# Domino_Pi_No_Teardrop.net
KiCad netlist of a schematic drawn in EAGLE
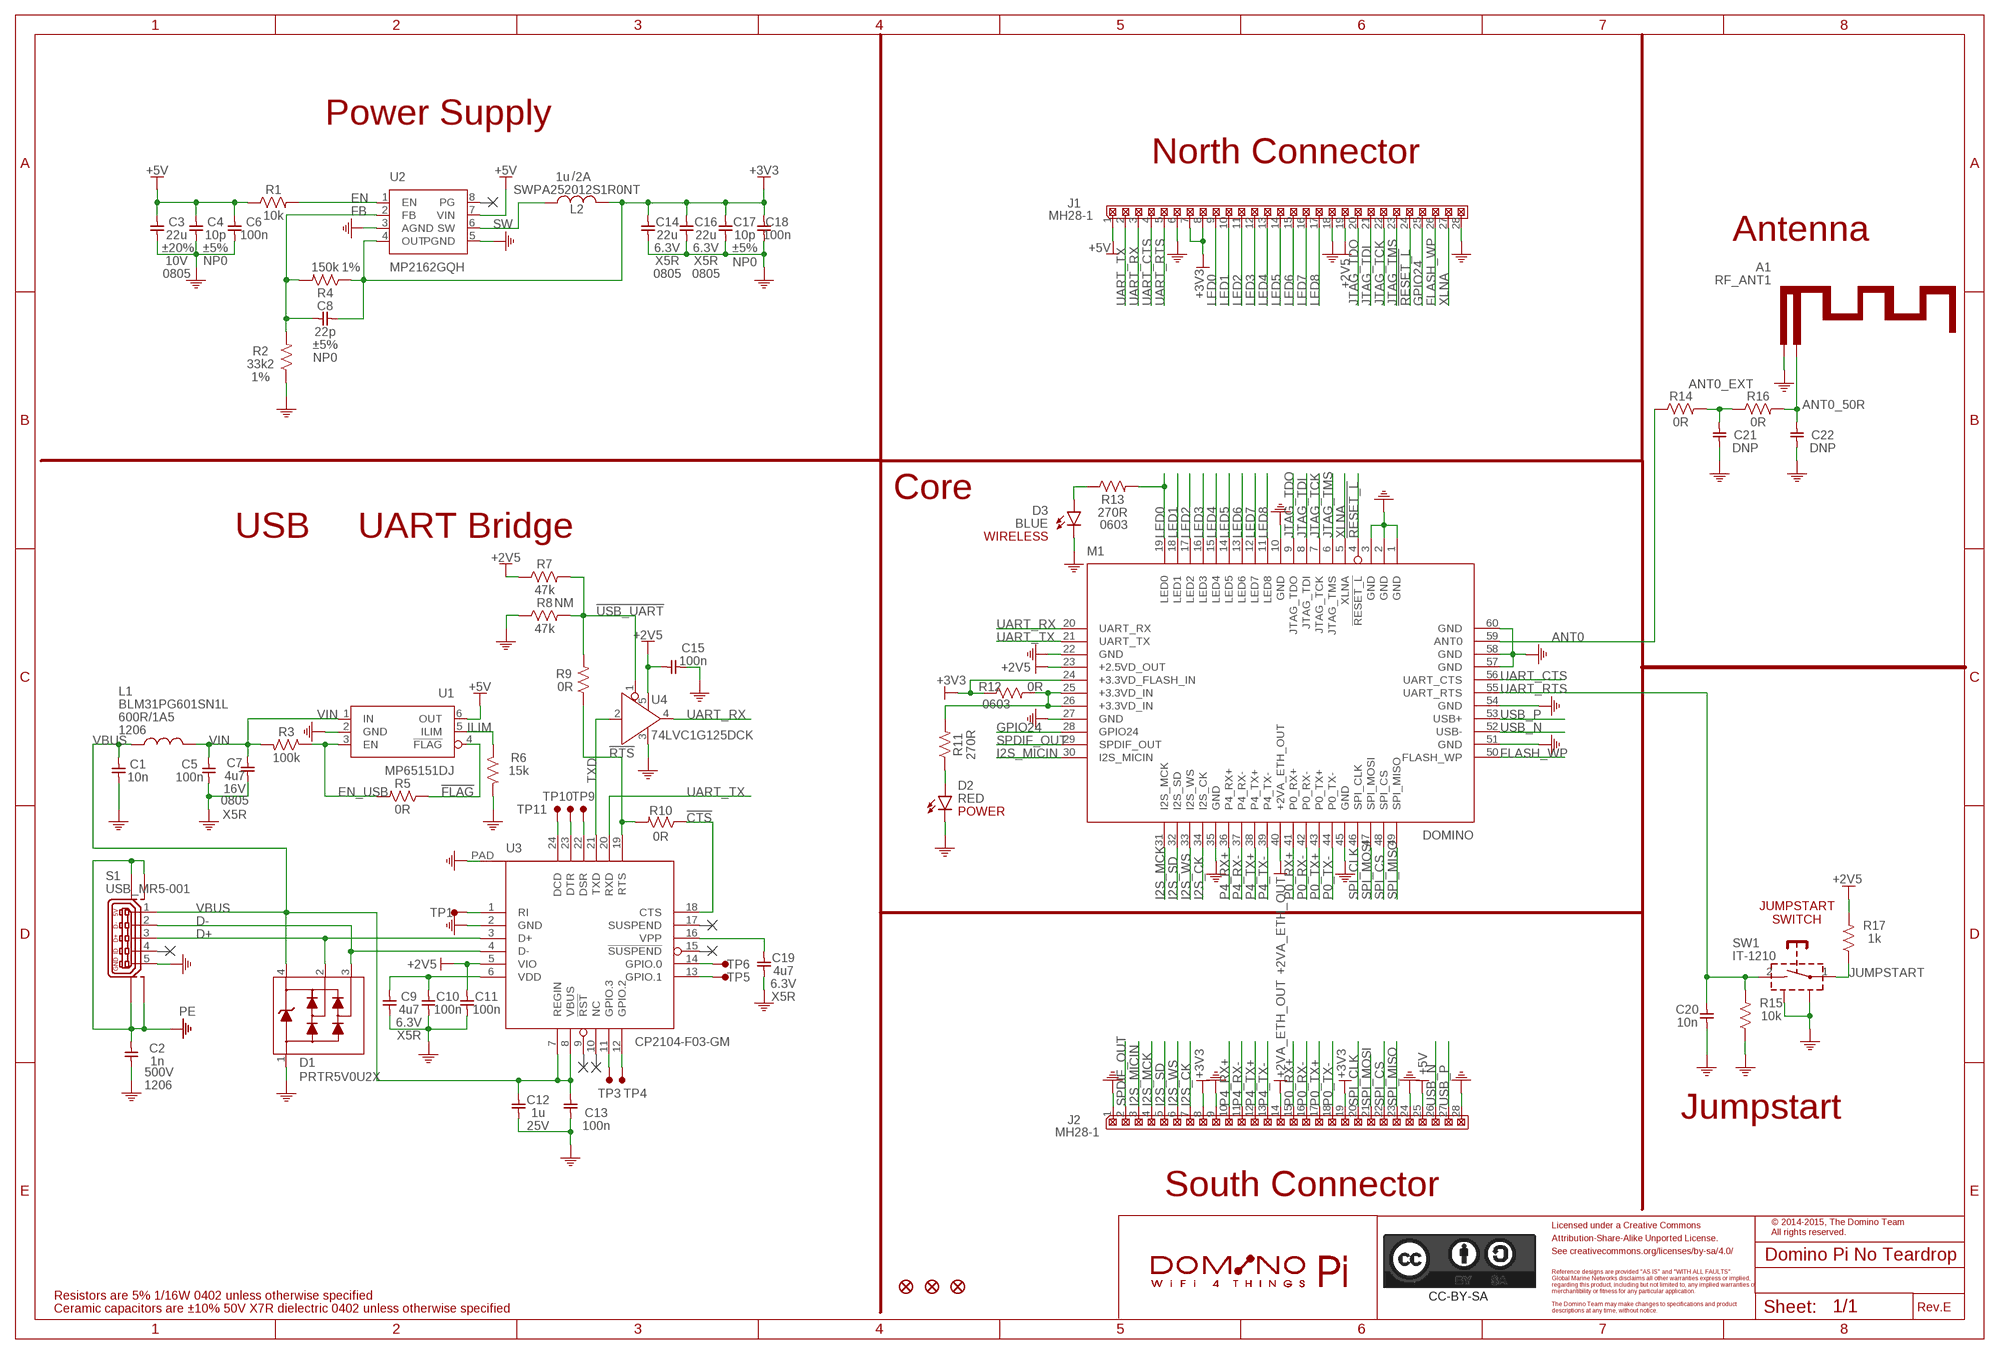
[diagram p0: schematic, sheet 1]

(export (version "E")
  (design (tool "Eeschema 10.0.6"))
  (components
    (comp (ref "A1")
      (value "RF_ANT1")
      (footprint "eagle-import:RF_ANT1")
      (fields (field (name "PARTNO") "WIFI_ANT-2.4GHz"))
      (libsource (lib "eagle-import") (part "RF_ANT1"))
    )
    (comp (ref "C1")
      (value "10n")
      (footprint "eagle-import:C0402")
      (fields (field (name "PARTNO") "C0402_10n_X7R_10%_CER_50V"))
      (libsource (lib "eagle-import") (part "CAP_0402"))
    )
    (comp (ref "C2")
      (value "1n")
      (footprint "eagle-import:C1206")
      (fields
        (field (name "SIZE") "1206")
        (field (name "PARTNO") "C1206_1n_X7R_10%_CER_500V")
        (field (name "VOLT") "500V")
      )
      (libsource (lib "eagle-import") (part "CAP_1206"))
    )
    (comp (ref "C3")
      (value "22u")
      (footprint "eagle-import:C0805")
      (fields
        (field (name "SIZE") "0805")
        (field (name "PARTNO") "C1206_22u_X7R_20%_CER_10V")
        (field (name "TOL") "±20%")
        (field (name "VOLT") "10V")
      )
      (libsource (lib "eagle-import") (part "CAP_0805"))
    )
    (comp (ref "C4")
      (value "10p")
      (footprint "eagle-import:C0402")
      (fields
        (field (name "PARTNO") "C0402_10p_NP0_5%_CER_50V")
        (field (name "TC") "NP0")
        (field (name "TOL") "±5%")
      )
      (libsource (lib "eagle-import") (part "CAP_0402"))
    )
    (comp (ref "C5")
      (value "100n")
      (footprint "eagle-import:C0402")
      (fields (field (name "PARTNO") "C0402_100n_X7R_10%_CER_50V"))
      (libsource (lib "eagle-import") (part "CAP_0402"))
    )
    (comp (ref "C6")
      (value "100n")
      (footprint "eagle-import:C0402")
      (fields (field (name "PARTNO") "C0402_100n_X7R_10%_CER_50V"))
      (libsource (lib "eagle-import") (part "CAP_0402"))
    )
    (comp (ref "C7")
      (value "4u7")
      (footprint "eagle-import:C0805")
      (fields
        (field (name "SIZE") "0805")
        (field (name "PARTNO") "C0805_4u7_X5R_10%_CER_16V")
        (field (name "TC") "X5R")
        (field (name "VOLT") "16V")
      )
      (libsource (lib "eagle-import") (part "CAP_0805"))
    )
    (comp (ref "C8")
      (value "22p")
      (footprint "eagle-import:C0402")
      (fields
        (field (name "PARTNO") "C0402_22p_NP0_5%_CER_50V")
        (field (name "TC") "NP0")
        (field (name "TOL") "±5%")
      )
      (libsource (lib "eagle-import") (part "CAP_0402"))
    )
    (comp (ref "C9")
      (value "4u7")
      (footprint "eagle-import:C0402")
      (fields
        (field (name "PARTNO") "C0402_4u7_X5R_10%_CER_6V3")
        (field (name "TC") "X5R")
        (field (name "VOLT") "6.3V")
      )
      (libsource (lib "eagle-import") (part "CAP_0402"))
    )
    (comp (ref "C10")
      (value "100n")
      (footprint "eagle-import:C0402")
      (fields (field (name "PARTNO") "C0402_100n_X7R_10%_CER_50V"))
      (libsource (lib "eagle-import") (part "CAP_0402"))
    )
    (comp (ref "C11")
      (value "100n")
      (footprint "eagle-import:C0402")
      (fields (field (name "PARTNO") "C0402_100n_X7R_10%_CER_50V"))
      (libsource (lib "eagle-import") (part "CAP_0402"))
    )
    (comp (ref "C12")
      (value "1u")
      (footprint "eagle-import:C0402")
      (fields (field (name "PARTNO") "C0402_1u_X7R_10%_CER_25V") (field (name "VOLT") "25V"))
      (libsource (lib "eagle-import") (part "CAP_0402"))
    )
    (comp (ref "C13")
      (value "100n")
      (footprint "eagle-import:C0402")
      (fields (field (name "PARTNO") "C0402_100n_X7R_10%_CER_50V"))
      (libsource (lib "eagle-import") (part "CAP_0402"))
    )
    (comp (ref "C14")
      (value "22u")
      (footprint "eagle-import:C0805")
      (fields
        (field (name "SIZE") "0805")
        (field (name "PARTNO") "C0805_22u_X5R_20%_CER_6V3")
        (field (name "TC") "X5R")
        (field (name "VOLT") "6.3V")
      )
      (libsource (lib "eagle-import") (part "CAP_0805"))
    )
    (comp (ref "C15")
      (value "100n")
      (footprint "eagle-import:C0402")
      (fields (field (name "PARTNO") "C0402_100n_X7R_10%_CER_50V"))
      (libsource (lib "eagle-import") (part "CAP_0402"))
    )
    (comp (ref "C16")
      (value "22u")
      (footprint "eagle-import:C0805")
      (fields
        (field (name "SIZE") "0805")
        (field (name "PARTNO") "C0805_22u_X5R_20%_CER_6V3")
        (field (name "TC") "X5R")
        (field (name "VOLT") "6.3V")
      )
      (libsource (lib "eagle-import") (part "CAP_0805"))
    )
    (comp (ref "C17")
      (value "10p")
      (footprint "eagle-import:C0402")
      (fields
        (field (name "PARTNO") "C0402_10p_NP0_5%_CER_50V")
        (field (name "TC") "NP0")
        (field (name "TOL") "±5%")
      )
      (libsource (lib "eagle-import") (part "CAP_0402"))
    )
    (comp (ref "C18")
      (value "100n")
      (footprint "eagle-import:C0402")
      (fields (field (name "PARTNO") "C0402_100n_X7R_10%_CER_50V"))
      (libsource (lib "eagle-import") (part "CAP_0402"))
    )
    (comp (ref "C19")
      (value "4u7")
      (footprint "eagle-import:C0402")
      (fields
        (field (name "PARTNO") "C0402_4u7_X5R_10%_CER_6V3")
        (field (name "TC") "X5R")
        (field (name "VOLT") "6.3V")
      )
      (libsource (lib "eagle-import") (part "CAP_0402"))
    )
    (comp (ref "C20")
      (value "10n")
      (footprint "eagle-import:C0402")
      (fields (field (name "PARTNO") "C0402_10n_X7R_10%_CER_50V"))
      (libsource (lib "eagle-import") (part "CAP_0402"))
    )
    (comp (ref "C21")
      (value "DNP")
      (footprint "eagle-import:C0402")
      (fields (field (name "PARTNO") "C0402_DNP"))
      (libsource (lib "eagle-import") (part "CAP_0402"))
    )
    (comp (ref "C22")
      (value "DNP")
      (footprint "eagle-import:C0402")
      (fields (field (name "PARTNO") "C0402_DNP"))
      (libsource (lib "eagle-import") (part "CAP_0402"))
    )
    (comp (ref "CC-BY-SA")
      (value "CC-BY-SA_LOGO")
      (footprint "eagle-import:CC-BY-SA_LOGO")
      (libsource (lib "eagle-import") (part "CC-BY-SA_LOGO"))
    )
    (comp (ref "D1")
      (value "PRTR5V0U2X")
      (footprint "eagle-import:SOT143B")
      (libsource (lib "eagle-import") (part "PRTR5V0U2X"))
    )
    (comp (ref "D2")
      (value "RED")
      (footprint "eagle-import:LED0402")
      (fields (field (name "PARTNO") "LED0402-RED"))
      (libsource (lib "eagle-import") (part "LED_0402"))
    )
    (comp (ref "D3")
      (value "BLUE")
      (footprint "eagle-import:LED0402")
      (fields (field (name "PARTNO") "LED0402-BLUE"))
      (libsource (lib "eagle-import") (part "LED_0402"))
    )
    (comp (ref "F1")
      (value "FIDUCIAL")
      (footprint "eagle-import:FIDUCIAL")
      (libsource (lib "eagle-import") (part "FIDUCIAL"))
    )
    (comp (ref "F2")
      (value "FIDUCIAL")
      (footprint "eagle-import:FIDUCIAL")
      (libsource (lib "eagle-import") (part "FIDUCIAL"))
    )
    (comp (ref "F3")
      (value "FIDUCIAL")
      (footprint "eagle-import:FIDUCIAL")
      (libsource (lib "eagle-import") (part "FIDUCIAL"))
    )
    (comp (ref "J1")
      (value "MH28-1")
      (footprint "eagle-import:MH28-1-0.1")
      (fields (field (name "PARTNO") "MH28-1-0.1"))
      (libsource (lib "eagle-import") (part "MH28-1"))
    )
    (comp (ref "J2")
      (value "MH28-1")
      (footprint "eagle-import:MH28-1-0.1")
      (fields (field (name "PARTNO") "MH28-1-0.1"))
      (libsource (lib "eagle-import") (part "MH28-1"))
    )
    (comp (ref "L1")
      (value "BLM31PG601SN1L")
      (footprint "eagle-import:FB1206")
      (fields (field (name "SIZE") "1206") (field (name "OPT") "600R/1A5"))
      (libsource (lib "eagle-import") (part "FB_1206"))
    )
    (comp (ref "L2")
      (value "SWPA252012S1R0NT")
      (footprint "eagle-import:SWPA252012S")
      (fields
        (field (name "INDUCTANCE") "1u")
        (field (name "RATE") "2A")
        (field (name "PARTNO") "SWPA252012SMT")
        (field (name "RATE_1") "2A")
      )
      (libsource (lib "eagle-import") (part "SWPA252012S?NT1R0"))
    )
    (comp (ref "M1")
      (value "DOMINO")
      (footprint "eagle-import:DOMINO")
      (fields (field (name "PARTNO") "DOMINO-CORE"))
      (libsource (lib "eagle-import") (part "DOMINO"))
    )
    (comp (ref "R1")
      (value "10k")
      (footprint "eagle-import:R0402")
      (fields (field (name "PARTNO") "R0402_10k_5%_62.5mW"))
      (libsource (lib "eagle-import") (part "RES_0402"))
    )
    (comp (ref "R2")
      (value "33k2")
      (footprint "eagle-import:R0402")
      (fields (field (name "PARTNO") "R0402_33k2_1%_62.5mW") (field (name "TOL") "1%"))
      (libsource (lib "eagle-import") (part "RES_0402"))
    )
    (comp (ref "R3")
      (value "100k")
      (footprint "eagle-import:R0402")
      (fields (field (name "PARTNO") "R0402_100k_5%_62.5mW"))
      (libsource (lib "eagle-import") (part "RES_0402"))
    )
    (comp (ref "R4")
      (value "150k")
      (footprint "eagle-import:R0402")
      (fields (field (name "PARTNO") "R0402_150k_1%_62.5mW") (field (name "TOL") "1%"))
      (libsource (lib "eagle-import") (part "RES_0402"))
    )
    (comp (ref "R5")
      (value "0R")
      (footprint "eagle-import:R0402")
      (fields (field (name "PARTNO") "R0402_0R_5%_62.5mW"))
      (libsource (lib "eagle-import") (part "RES_0402"))
    )
    (comp (ref "R6")
      (value "15k")
      (footprint "eagle-import:R0402")
      (fields (field (name "PARTNO") "R0402_15k_5%_62.5mW"))
      (libsource (lib "eagle-import") (part "RES_0402"))
    )
    (comp (ref "R7")
      (value "47k")
      (footprint "eagle-import:R0402")
      (fields (field (name "PARTNO") "R0402_47k_5%_62.5mW"))
      (libsource (lib "eagle-import") (part "RES_0402"))
    )
    (comp (ref "R8")
      (value "47k")
      (footprint "eagle-import:R0402")
      (fields (field (name "PARTNO") "R0402_47k_5%_62.5mW"))
      (libsource (lib "eagle-import") (part "RES_0402"))
    )
    (comp (ref "R9")
      (value "0R")
      (footprint "eagle-import:R0402")
      (fields (field (name "PARTNO") "R0402_0R_5%_62.5mW"))
      (libsource (lib "eagle-import") (part "RES_0402"))
    )
    (comp (ref "R10")
      (value "0R")
      (footprint "eagle-import:R0402")
      (fields (field (name "PARTNO") "R0402_0R_5%_62.5mW"))
      (libsource (lib "eagle-import") (part "RES_0402"))
    )
    (comp (ref "R11")
      (value "270R")
      (footprint "eagle-import:R0402")
      (fields (field (name "PARTNO") "R0402_270R_5%_62.5mW"))
      (libsource (lib "eagle-import") (part "RES_0402"))
    )
    (comp (ref "R12")
      (value "0R")
      (footprint "eagle-import:R0603")
      (fields (field (name "SIZE") "0603") (field (name "PARTNO") "R0603_0R_5%_125mW"))
      (libsource (lib "eagle-import") (part "RES_0603"))
    )
    (comp (ref "R13")
      (value "270R")
      (footprint "eagle-import:R0603")
      (fields (field (name "SIZE") "0603") (field (name "PARTNO") "R0603_270R_5%_125mW"))
      (libsource (lib "eagle-import") (part "RES_0603"))
    )
    (comp (ref "R14")
      (value "0R")
      (footprint "eagle-import:R0402")
      (fields (field (name "PARTNO") "R0402_0R_5%_62.5mW"))
      (libsource (lib "eagle-import") (part "RES_0402"))
    )
    (comp (ref "R15")
      (value "10k")
      (footprint "eagle-import:R0402")
      (fields (field (name "PARTNO") "R0402_10k_5%_62.5mW"))
      (libsource (lib "eagle-import") (part "RES_0402"))
    )
    (comp (ref "R16")
      (value "0R")
      (footprint "eagle-import:R0402")
      (fields (field (name "PARTNO") "R0402_0R_5%_62.5mW"))
      (libsource (lib "eagle-import") (part "RES_0402"))
    )
    (comp (ref "R17")
      (value "1k")
      (footprint "eagle-import:R0402")
      (fields (field (name "PARTNO") "R0402_1k_5%_62.5mW"))
      (libsource (lib "eagle-import") (part "RES_0402"))
    )
    (comp (ref "S1")
      (value "USB_MR5-001")
      (footprint "eagle-import:USB-MR5-001")
      (fields (field (name "PARTNO") "USB MR5-001"))
      (libsource (lib "eagle-import") (part "USB_MR5-001"))
    )
    (comp (ref "SW1")
      (value "IT-1210")
      (footprint "eagle-import:IT-1210")
      (libsource (lib "eagle-import") (part "IT-1210"))
    )
    (comp (ref "TP1")
      (value "TEST_PAD")
      (footprint "eagle-import:TEST_PAD")
      (libsource (lib "eagle-import") (part "TEST_PAD"))
    )
    (comp (ref "TP3")
      (value "TEST_PAD")
      (footprint "eagle-import:TEST_PAD")
      (libsource (lib "eagle-import") (part "TEST_PAD"))
    )
    (comp (ref "TP4")
      (value "TEST_PAD")
      (footprint "eagle-import:TEST_PAD")
      (libsource (lib "eagle-import") (part "TEST_PAD"))
    )
    (comp (ref "TP5")
      (value "TEST_PAD")
      (footprint "eagle-import:TEST_PAD")
      (libsource (lib "eagle-import") (part "TEST_PAD"))
    )
    (comp (ref "TP6")
      (value "TEST_PAD")
      (footprint "eagle-import:TEST_PAD")
      (libsource (lib "eagle-import") (part "TEST_PAD"))
    )
    (comp (ref "TP9")
      (value "TEST_PAD")
      (footprint "eagle-import:TEST_PAD")
      (libsource (lib "eagle-import") (part "TEST_PAD"))
    )
    (comp (ref "TP10")
      (value "TEST_PAD")
      (footprint "eagle-import:TEST_PAD")
      (libsource (lib "eagle-import") (part "TEST_PAD"))
    )
    (comp (ref "TP11")
      (value "TEST_PAD")
      (footprint "eagle-import:TEST_PAD")
      (libsource (lib "eagle-import") (part "TEST_PAD"))
    )
    (comp (ref "U1")
      (value "MP65151DJ")
      (footprint "eagle-import:SOT23-6")
      (libsource (lib "eagle-import") (part "MP65151DJ"))
    )
    (comp (ref "U2")
      (value "MP2162GQH")
      (footprint "eagle-import:QFN-8_2X1.5")
      (libsource (lib "eagle-import") (part "MP2162GQH"))
    )
    (comp (ref "U3")
      (value "CP2104-F03-GM")
      (footprint "eagle-import:QFN-25_4X4")
      (libsource (lib "eagle-import") (part "CP2104-F03-GM"))
    )
    (comp (ref "U4")
      (value "74LVC1G125DCK")
      (footprint "eagle-import:SC70")
      (fields (field (name "PARTNO") "74LVC1G125DCK "))
      (libsource (lib "eagle-import") (part "741G125DCKLVC"))
    )
    (comp (ref "W1")
      (value "DOMINO_PI_LOGO")
      (footprint "eagle-import:DOMINO_PI_LOGO")
      (libsource (lib "eagle-import") (part "DOMINO_PI_LOGO"))
    )
  )
  (nets
    (net (code "1") (name "+2V5") (class "Default")
      (node (ref "C11") (pin "1") (pinfunction "1_1") (pintype "passive"))
      (node (ref "C15") (pin "2") (pinfunction "2_2") (pintype "passive"))
      (node (ref "J1") (pin "19") (pinfunction "19_19") (pintype "passive"))
      (node (ref "M1") (pin "23") (pinfunction "+2.5VD_OUT_23") (pintype "power_in"))
      (node (ref "R17") (pin "2") (pinfunction "2_2") (pintype "passive"))
      (node (ref "R7") (pin "1") (pinfunction "1_1") (pintype "passive"))
      (node (ref "U3") (pin "5") (pinfunction "VIO_5") (pintype "power_in"))
      (node (ref "U4") (pin "5") (pinfunction "VCC_5") (pintype "power_in"))
    )
    (net (code "2") (name "+2VA_ETH_OUT") (class "Default")
      (node (ref "J2") (pin "14") (pinfunction "14_14") (pintype "passive"))
      (node (ref "M1") (pin "40") (pinfunction "+2VA_ETH_OUT_40") (pintype "power_in"))
    )
    (net (code "3") (name "+3V3") (class "Default")
      (node (ref "C14") (pin "1") (pinfunction "1_1") (pintype "passive"))
      (node (ref "C16") (pin "1") (pinfunction "1_1") (pintype "passive"))
      (node (ref "C17") (pin "1") (pinfunction "1_1") (pintype "passive"))
      (node (ref "C18") (pin "1") (pinfunction "1_1") (pintype "passive"))
      (node (ref "C8") (pin "2") (pinfunction "2_2") (pintype "passive"))
      (node (ref "J1") (pin "7") (pinfunction "7_7") (pintype "passive"))
      (node (ref "J1") (pin "8") (pinfunction "8_8") (pintype "passive"))
      (node (ref "J2") (pin "19") (pinfunction "19_19") (pintype "passive"))
      (node (ref "J2") (pin "8") (pinfunction "8_8") (pintype "passive"))
      (node (ref "L2") (pin "2") (pinfunction "2_2") (pintype "passive"))
      (node (ref "M1") (pin "24") (pinfunction "+3.3VD_FLASH_IN_24") (pintype "power_in"))
      (node (ref "R12") (pin "1") (pinfunction "1_1") (pintype "passive"))
      (node (ref "R4") (pin "1") (pinfunction "1_1") (pintype "passive"))
      (node (ref "U2") (pin "4") (pinfunction "OUT_4") (pintype "power_in"))
    )
    (net (code "4") (name "+5V") (class "Default")
      (node (ref "C3") (pin "1") (pinfunction "1_1") (pintype "passive"))
      (node (ref "C4") (pin "1") (pinfunction "1_1") (pintype "passive"))
      (node (ref "C6") (pin "1") (pinfunction "1_1") (pintype "passive"))
      (node (ref "J1") (pin "1") (pinfunction "1_1") (pintype "passive"))
      (node (ref "J2") (pin "25") (pinfunction "25_25") (pintype "passive"))
      (node (ref "R1") (pin "1") (pinfunction "1_1") (pintype "passive"))
      (node (ref "U1") (pin "6") (pinfunction "OUT_6") (pintype "power_in"))
      (node (ref "U2") (pin "7") (pinfunction "VIN_7") (pintype "power_in"))
    )
    (net (code "5") (name "/ANT0") (class "Default")
      (node (ref "M1") (pin "59") (pinfunction "ANT0_59") (pintype "passive"))
      (node (ref "R14") (pin "1") (pinfunction "1_1") (pintype "passive"))
    )
    (net (code "6") (name "/ANT0_50R") (class "Default")
      (node (ref "A1") (pin "FEED") (pinfunction "FEED_FEED") (pintype "passive"))
      (node (ref "C22") (pin "1") (pinfunction "1_1") (pintype "passive"))
      (node (ref "R16") (pin "2") (pinfunction "2_2") (pintype "passive"))
    )
    (net (code "7") (name "/ANT0_EXT") (class "Default")
      (node (ref "C21") (pin "1") (pinfunction "1_1") (pintype "passive"))
      (node (ref "R14") (pin "2") (pinfunction "2_2") (pintype "passive"))
      (node (ref "R16") (pin "1") (pinfunction "1_1") (pintype "passive"))
    )
    (net (code "8") (name "/D+") (class "Default")
      (node (ref "D1") (pin "2") (pinfunction "P$2_2") (pintype "passive"))
      (node (ref "S1") (pin "3") (pinfunction "3_3") (pintype "passive"))
      (node (ref "U3") (pin "3") (pinfunction "D+_3") (pintype "passive"))
    )
    (net (code "9") (name "/D-") (class "Default")
      (node (ref "D1") (pin "3") (pinfunction "P$3_3") (pintype "passive"))
      (node (ref "S1") (pin "2") (pinfunction "2_2") (pintype "passive"))
      (node (ref "U3") (pin "4") (pinfunction "D-_4") (pintype "passive"))
    )
    (net (code "10") (name "/EN") (class "Default")
      (node (ref "R1") (pin "2") (pinfunction "2_2") (pintype "passive"))
      (node (ref "U2") (pin "1") (pinfunction "EN_1") (pintype "input"))
    )
    (net (code "11") (name "/EN_USB") (class "Default")
      (node (ref "R3") (pin "1") (pinfunction "1_1") (pintype "passive"))
      (node (ref "R5") (pin "2") (pinfunction "2_2") (pintype "passive"))
      (node (ref "U1") (pin "3") (pinfunction "EN_3") (pintype "input"))
    )
    (net (code "12") (name "/FB") (class "Default")
      (node (ref "C8") (pin "1") (pinfunction "1_1") (pintype "passive"))
      (node (ref "R2") (pin "2") (pinfunction "2_2") (pintype "passive"))
      (node (ref "R4") (pin "2") (pinfunction "2_2") (pintype "passive"))
      (node (ref "U2") (pin "2") (pinfunction "FB_2") (pintype "passive"))
    )
    (net (code "13") (name "/FLASH_WP") (class "Default")
      (node (ref "J1") (pin "26") (pinfunction "26_26") (pintype "passive"))
      (node (ref "M1") (pin "50") (pinfunction "FLASH_WP_50") (pintype "bidirectional"))
    )
    (net (code "14") (name "/GPIO24") (class "Default")
      (node (ref "J1") (pin "25") (pinfunction "25_25") (pintype "passive"))
      (node (ref "M1") (pin "28") (pinfunction "GPIO24_28") (pintype "bidirectional"))
    )
    (net (code "15") (name "/I2S_CK") (class "Default")
      (node (ref "J2") (pin "7") (pinfunction "7_7") (pintype "passive"))
      (node (ref "M1") (pin "34") (pinfunction "I2S_CK_34") (pintype "bidirectional"))
    )
    (net (code "16") (name "/I2S_MCK") (class "Default")
      (node (ref "J2") (pin "4") (pinfunction "4_4") (pintype "passive"))
      (node (ref "M1") (pin "31") (pinfunction "I2S_MCK_31") (pintype "bidirectional"))
    )
    (net (code "17") (name "/I2S_MICIN") (class "Default")
      (node (ref "J2") (pin "3") (pinfunction "3_3") (pintype "passive"))
      (node (ref "M1") (pin "30") (pinfunction "I2S_MICIN_30") (pintype "bidirectional"))
    )
    (net (code "18") (name "/I2S_SD") (class "Default")
      (node (ref "J2") (pin "5") (pinfunction "5_5") (pintype "passive"))
      (node (ref "M1") (pin "32") (pinfunction "I2S_SD_32") (pintype "bidirectional"))
    )
    (net (code "19") (name "/I2S_WS") (class "Default")
      (node (ref "J2") (pin "6") (pinfunction "6_6") (pintype "passive"))
      (node (ref "M1") (pin "33") (pinfunction "I2S_WS_33") (pintype "bidirectional"))
    )
    (net (code "20") (name "/ILIM") (class "Default")
      (node (ref "R6") (pin "1") (pinfunction "1_1") (pintype "passive"))
      (node (ref "U1") (pin "5") (pinfunction "ILIM_5") (pintype "passive"))
    )
    (net (code "21") (name "/JTAG_TCK") (class "Default")
      (node (ref "J1") (pin "22") (pinfunction "22_22") (pintype "passive"))
      (node (ref "M1") (pin "7") (pinfunction "JTAG_TCK_7") (pintype "bidirectional"))
    )
    (net (code "22") (name "/JTAG_TDI") (class "Default")
      (node (ref "J1") (pin "21") (pinfunction "21_21") (pintype "passive"))
      (node (ref "M1") (pin "8") (pinfunction "JTAG_TDI_8") (pintype "bidirectional"))
    )
    (net (code "23") (name "/JTAG_TDO") (class "Default")
      (node (ref "J1") (pin "20") (pinfunction "20_20") (pintype "passive"))
      (node (ref "M1") (pin "9") (pinfunction "JTAG_TDO_9") (pintype "bidirectional"))
    )
    (net (code "24") (name "/JTAG_TMS") (class "Default")
      (node (ref "J1") (pin "23") (pinfunction "23_23") (pintype "passive"))
      (node (ref "M1") (pin "6") (pinfunction "JTAG_TMS_6") (pintype "bidirectional"))
    )
    (net (code "25") (name "/JUMPSTART") (class "Default")
      (node (ref "R17") (pin "1") (pinfunction "1_1") (pintype "passive"))
      (node (ref "SW1") (pin "1") (pinfunction "1_1") (pintype "passive"))
    )
    (net (code "26") (name "/LED0") (class "Default")
      (node (ref "J1") (pin "9") (pinfunction "9_9") (pintype "passive"))
      (node (ref "M1") (pin "19") (pinfunction "LED0_19") (pintype "bidirectional"))
      (node (ref "R13") (pin "2") (pinfunction "2_2") (pintype "passive"))
    )
    (net (code "27") (name "/LED1") (class "Default")
      (node (ref "J1") (pin "10") (pinfunction "10_10") (pintype "passive"))
      (node (ref "M1") (pin "18") (pinfunction "LED1_18") (pintype "bidirectional"))
    )
    (net (code "28") (name "/LED2") (class "Default")
      (node (ref "J1") (pin "11") (pinfunction "11_11") (pintype "passive"))
      (node (ref "M1") (pin "17") (pinfunction "LED2_17") (pintype "bidirectional"))
    )
    (net (code "29") (name "/LED3") (class "Default")
      (node (ref "J1") (pin "12") (pinfunction "12_12") (pintype "passive"))
      (node (ref "M1") (pin "16") (pinfunction "LED3_16") (pintype "bidirectional"))
    )
    (net (code "30") (name "/LED4") (class "Default")
      (node (ref "J1") (pin "13") (pinfunction "13_13") (pintype "passive"))
      (node (ref "M1") (pin "15") (pinfunction "LED4_15") (pintype "bidirectional"))
    )
    (net (code "31") (name "/LED5") (class "Default")
      (node (ref "J1") (pin "14") (pinfunction "14_14") (pintype "passive"))
      (node (ref "M1") (pin "14") (pinfunction "LED5_14") (pintype "bidirectional"))
    )
    (net (code "32") (name "/LED6") (class "Default")
      (node (ref "J1") (pin "15") (pinfunction "15_15") (pintype "passive"))
      (node (ref "M1") (pin "13") (pinfunction "LED6_13") (pintype "bidirectional"))
    )
    (net (code "33") (name "/LED7") (class "Default")
      (node (ref "J1") (pin "16") (pinfunction "16_16") (pintype "passive"))
      (node (ref "M1") (pin "12") (pinfunction "LED7_12") (pintype "bidirectional"))
    )
    (net (code "34") (name "/LED8") (class "Default")
      (node (ref "J1") (pin "17") (pinfunction "17_17") (pintype "passive"))
      (node (ref "M1") (pin "11") (pinfunction "LED8_11") (pintype "bidirectional"))
    )
    (net (code "35") (name "/P0_RX+") (class "Default")
      (node (ref "J2") (pin "15") (pinfunction "15_15") (pintype "passive"))
      (node (ref "M1") (pin "41") (pinfunction "P0_RX+_41") (pintype "passive"))
    )
    (net (code "36") (name "/P0_RX-") (class "Default")
      (node (ref "J2") (pin "16") (pinfunction "16_16") (pintype "passive"))
      (node (ref "M1") (pin "42") (pinfunction "P0_RX-_42") (pintype "passive"))
    )
    (net (code "37") (name "/P0_TX+") (class "Default")
      (node (ref "J2") (pin "17") (pinfunction "17_17") (pintype "passive"))
      (node (ref "M1") (pin "43") (pinfunction "P0_TX+_43") (pintype "passive"))
    )
    (net (code "38") (name "/P0_TX-") (class "Default")
      (node (ref "J2") (pin "18") (pinfunction "18_18") (pintype "passive"))
      (node (ref "M1") (pin "44") (pinfunction "P0_TX-_44") (pintype "passive"))
    )
    (net (code "39") (name "/P4_RX+") (class "Default")
      (node (ref "J2") (pin "10") (pinfunction "10_10") (pintype "passive"))
      (node (ref "M1") (pin "36") (pinfunction "P4_RX+_36") (pintype "passive"))
    )
    (net (code "40") (name "/P4_RX-") (class "Default")
      (node (ref "J2") (pin "11") (pinfunction "11_11") (pintype "passive"))
      (node (ref "M1") (pin "37") (pinfunction "P4_RX-_37") (pintype "passive"))
    )
    (net (code "41") (name "/P4_TX+") (class "Default")
      (node (ref "J2") (pin "12") (pinfunction "12_12") (pintype "passive"))
      (node (ref "M1") (pin "38") (pinfunction "P4_TX+_38") (pintype "passive"))
    )
    (net (code "42") (name "/P4_TX-") (class "Default")
      (node (ref "J2") (pin "13") (pinfunction "13_13") (pintype "passive"))
      (node (ref "M1") (pin "39") (pinfunction "P4_TX-_39") (pintype "passive"))
    )
    (net (code "43") (name "/SPDIF_OUT") (class "Default")
      (node (ref "J2") (pin "2") (pinfunction "2_2") (pintype "passive"))
      (node (ref "M1") (pin "29") (pinfunction "SPDIF_OUT_29") (pintype "bidirectional"))
    )
    (net (code "44") (name "/SPI_CLK") (class "Default")
      (node (ref "J2") (pin "20") (pinfunction "20_20") (pintype "passive"))
      (node (ref "M1") (pin "46") (pinfunction "SPI_CLK_46") (pintype "bidirectional"))
    )
    (net (code "45") (name "/SPI_CS") (class "Default")
      (node (ref "J2") (pin "22") (pinfunction "22_22") (pintype "passive"))
      (node (ref "M1") (pin "48") (pinfunction "SPI_CS_48") (pintype "bidirectional"))
    )
    (net (code "46") (name "/SPI_MISO") (class "Default")
      (node (ref "J2") (pin "23") (pinfunction "23_23") (pintype "passive"))
      (node (ref "M1") (pin "49") (pinfunction "SPI_MISO_49") (pintype "bidirectional"))
    )
    (net (code "47") (name "/SPI_MOSI") (class "Default")
      (node (ref "J2") (pin "21") (pinfunction "21_21") (pintype "passive"))
      (node (ref "M1") (pin "47") (pinfunction "SPI_MOSI_47") (pintype "bidirectional"))
    )
    (net (code "48") (name "/SW") (class "Default")
      (node (ref "L2") (pin "1") (pinfunction "1_1") (pintype "passive"))
      (node (ref "U2") (pin "6") (pinfunction "SW_6") (pintype "passive"))
    )
    (net (code "49") (name "/TXD") (class "Default")
      (node (ref "U3") (pin "21") (pinfunction "TXD_21") (pintype "output"))
      (node (ref "U4") (pin "2") (pinfunction "A_2") (pintype "input"))
    )
    (net (code "50") (name "/UART_CTS") (class "Default")
      (node (ref "J1") (pin "4") (pinfunction "4_4") (pintype "passive"))
      (node (ref "M1") (pin "56") (pinfunction "UART_CTS_56") (pintype "bidirectional"))
    )
    (net (code "51") (name "/UART_RTS") (class "Default")
      (node (ref "C20") (pin "1") (pinfunction "1_1") (pintype "passive"))
      (node (ref "J1") (pin "5") (pinfunction "5_5") (pintype "passive"))
      (node (ref "M1") (pin "55") (pinfunction "UART_RTS_55") (pintype "bidirectional"))
      (node (ref "R15") (pin "2") (pinfunction "2_2") (pintype "passive"))
      (node (ref "SW1") (pin "2") (pinfunction "2_2") (pintype "passive"))
    )
    (net (code "52") (name "/UART_RX") (class "Default")
      (node (ref "J1") (pin "3") (pinfunction "3_3") (pintype "passive"))
      (node (ref "M1") (pin "20") (pinfunction "UART_RX_20") (pintype "bidirectional"))
      (node (ref "U4") (pin "4") (pinfunction "Y_4") (pintype "tri_state"))
    )
    (net (code "53") (name "/UART_TX") (class "Default")
      (node (ref "J1") (pin "2") (pinfunction "2_2") (pintype "passive"))
      (node (ref "M1") (pin "21") (pinfunction "UART_TX_21") (pintype "bidirectional"))
      (node (ref "U3") (pin "20") (pinfunction "RXD_20") (pintype "input"))
    )
    (net (code "54") (name "/USB_N") (class "Default")
      (node (ref "J2") (pin "26") (pinfunction "26_26") (pintype "passive"))
      (node (ref "M1") (pin "52") (pinfunction "USB-_52") (pintype "passive"))
    )
    (net (code "55") (name "/USB_P") (class "Default")
      (node (ref "J2") (pin "27") (pinfunction "27_27") (pintype "passive"))
      (node (ref "M1") (pin "53") (pinfunction "USB+_53") (pintype "passive"))
    )
    (net (code "56") (name "/VBUS") (class "Default")
      (node (ref "C1") (pin "1") (pinfunction "1_1") (pintype "passive"))
      (node (ref "C12") (pin "1") (pinfunction "1_1") (pintype "passive"))
      (node (ref "C13") (pin "1") (pinfunction "1_1") (pintype "passive"))
      (node (ref "D1") (pin "4") (pinfunction "P$4_4") (pintype "passive"))
      (node (ref "L1") (pin "2") (pinfunction "2_2") (pintype "passive"))
      (node (ref "S1") (pin "1") (pinfunction "1_1") (pintype "passive"))
      (node (ref "U3") (pin "7") (pinfunction "REGIN_7") (pintype "power_in"))
      (node (ref "U3") (pin "8") (pinfunction "VBUS_8") (pintype "input"))
    )
    (net (code "57") (name "/VIN") (class "Default")
      (node (ref "C5") (pin "1") (pinfunction "1_1") (pintype "passive"))
      (node (ref "C7") (pin "1") (pinfunction "1_1") (pintype "passive"))
      (node (ref "L1") (pin "1") (pinfunction "1_1") (pintype "passive"))
      (node (ref "R3") (pin "2") (pinfunction "2_2") (pintype "passive"))
      (node (ref "U1") (pin "1") (pinfunction "IN_1") (pintype "power_in"))
    )
    (net (code "58") (name "/XLNA") (class "Default")
      (node (ref "J1") (pin "27") (pinfunction "27_27") (pintype "passive"))
      (node (ref "M1") (pin "5") (pinfunction "XLNA_5") (pintype "bidirectional"))
    )
    (net (code "59") (name "/~{CTS}") (class "Default")
      (node (ref "R10") (pin "1") (pinfunction "1_1") (pintype "passive"))
      (node (ref "U3") (pin "18") (pinfunction "CTS_18") (pintype "input"))
    )
    (net (code "60") (name "/~{FLAG}") (class "Default")
      (node (ref "R5") (pin "1") (pinfunction "1_1") (pintype "passive"))
      (node (ref "U1") (pin "4") (pinfunction "~{FLAG}_4") (pintype "open_collector"))
    )
    (net (code "61") (name "/~{RESET_L}") (class "Default")
      (node (ref "J1") (pin "24") (pinfunction "24_24") (pintype "passive"))
      (node (ref "M1") (pin "4") (pinfunction "~{RESET_L}_4") (pintype "input"))
    )
    (net (code "62") (name "/~{RTS}") (class "Default")
      (node (ref "R10") (pin "2") (pinfunction "2_2") (pintype "passive"))
      (node (ref "R9") (pin "1") (pinfunction "1_1") (pintype "passive"))
      (node (ref "U3") (pin "19") (pinfunction "RTS_19") (pintype "output"))
    )
    (net (code "63") (name "/~{USB_UART}") (class "Default")
      (node (ref "R7") (pin "2") (pinfunction "2_2") (pintype "passive"))
      (node (ref "R8") (pin "2") (pinfunction "2_2") (pintype "passive"))
      (node (ref "R9") (pin "2") (pinfunction "2_2") (pintype "passive"))
      (node (ref "U4") (pin "1") (pinfunction "~{OE}_1") (pintype "input"))
    )
    (net (code "64") (name "GND") (class "Default")
      (node (ref "A1") (pin "GND") (pinfunction "GND_GND") (pintype "power_in"))
      (node (ref "C1") (pin "2") (pinfunction "2_2") (pintype "passive"))
      (node (ref "C10") (pin "2") (pinfunction "2_2") (pintype "passive"))
      (node (ref "C11") (pin "2") (pinfunction "2_2") (pintype "passive"))
      (node (ref "C12") (pin "2") (pinfunction "2_2") (pintype "passive"))
      (node (ref "C13") (pin "2") (pinfunction "2_2") (pintype "passive"))
      (node (ref "C14") (pin "2") (pinfunction "2_2") (pintype "passive"))
      (node (ref "C15") (pin "1") (pinfunction "1_1") (pintype "passive"))
      (node (ref "C16") (pin "2") (pinfunction "2_2") (pintype "passive"))
      (node (ref "C17") (pin "2") (pinfunction "2_2") (pintype "passive"))
      (node (ref "C18") (pin "2") (pinfunction "2_2") (pintype "passive"))
      (node (ref "C19") (pin "2") (pinfunction "2_2") (pintype "passive"))
      (node (ref "C2") (pin "2") (pinfunction "2_2") (pintype "passive"))
      (node (ref "C20") (pin "2") (pinfunction "2_2") (pintype "passive"))
      (node (ref "C21") (pin "2") (pinfunction "2_2") (pintype "passive"))
      (node (ref "C22") (pin "2") (pinfunction "2_2") (pintype "passive"))
      (node (ref "C3") (pin "2") (pinfunction "2_2") (pintype "passive"))
      (node (ref "C4") (pin "2") (pinfunction "2_2") (pintype "passive"))
      (node (ref "C5") (pin "2") (pinfunction "2_2") (pintype "passive"))
      (node (ref "C6") (pin "2") (pinfunction "2_2") (pintype "passive"))
      (node (ref "C7") (pin "2") (pinfunction "2_2") (pintype "passive"))
      (node (ref "C9") (pin "2") (pinfunction "2_2") (pintype "passive"))
      (node (ref "D1") (pin "1") (pinfunction "P$1_1") (pintype "passive"))
      (node (ref "D2") (pin "1") (pinfunction "C_1") (pintype "passive"))
      (node (ref "D3") (pin "1") (pinfunction "C_1") (pintype "passive"))
      (node (ref "J1") (pin "18") (pinfunction "18_18") (pintype "passive"))
      (node (ref "J1") (pin "28") (pinfunction "28_28") (pintype "passive"))
      (node (ref "J1") (pin "6") (pinfunction "6_6") (pintype "passive"))
      (node (ref "J2") (pin "1") (pinfunction "1_1") (pintype "passive"))
      (node (ref "J2") (pin "24") (pinfunction "24_24") (pintype "passive"))
      (node (ref "J2") (pin "28") (pinfunction "28_28") (pintype "passive"))
      (node (ref "J2") (pin "9") (pinfunction "9_9") (pintype "passive"))
      (node (ref "M1") (pin "1") (pinfunction "GND_1") (pintype "power_in"))
      (node (ref "M1") (pin "10") (pinfunction "GND_10") (pintype "power_in"))
      (node (ref "M1") (pin "2") (pinfunction "GND_2") (pintype "power_in"))
      (node (ref "M1") (pin "22") (pinfunction "GND_22") (pintype "power_in"))
      (node (ref "M1") (pin "27") (pinfunction "GND_27") (pintype "power_in"))
      (node (ref "M1") (pin "3") (pinfunction "GND_3") (pintype "power_in"))
      (node (ref "M1") (pin "35") (pinfunction "GND_35") (pintype "power_in"))
      (node (ref "M1") (pin "45") (pinfunction "GND_45") (pintype "power_in"))
      (node (ref "M1") (pin "51") (pinfunction "GND_51") (pintype "power_in"))
      (node (ref "M1") (pin "54") (pinfunction "GND_54") (pintype "power_in"))
      (node (ref "M1") (pin "57") (pinfunction "GND_57") (pintype "power_in"))
      (node (ref "M1") (pin "58") (pinfunction "GND_58") (pintype "power_in"))
      (node (ref "M1") (pin "60") (pinfunction "GND_60") (pintype "power_in"))
      (node (ref "R15") (pin "1") (pinfunction "1_1") (pintype "passive"))
      (node (ref "R2") (pin "1") (pinfunction "1_1") (pintype "passive"))
      (node (ref "R6") (pin "2") (pinfunction "2_2") (pintype "passive"))
      (node (ref "R8") (pin "1") (pinfunction "1_1") (pintype "passive"))
      (node (ref "S1") (pin "5") (pinfunction "5_5") (pintype "passive"))
      (node (ref "SW1") (pin "SH$1") (pinfunction "SH$1_SH$1") (pintype "passive"))
      (node (ref "SW1") (pin "SH$2") (pinfunction "SH$2_SH$2") (pintype "passive"))
      (node (ref "U1") (pin "2") (pinfunction "GND_2") (pintype "power_in"))
      (node (ref "U2") (pin "3") (pinfunction "AGND_3") (pintype "power_in"))
      (node (ref "U2") (pin "5") (pinfunction "PGND_5") (pintype "power_in"))
      (node (ref "U3") (pin "2") (pinfunction "GND_2") (pintype "power_in"))
      (node (ref "U3") (pin "PAD") (pinfunction "PAD_PAD") (pintype "power_in"))
      (node (ref "U4") (pin "3") (pinfunction "GND_3") (pintype "power_in"))
    )
    (net (code "65") (name "Net-(D2-A)") (class "Default")
      (node (ref "D2") (pin "2") (pinfunction "A_2") (pintype "passive"))
      (node (ref "R11") (pin "1") (pinfunction "1_1") (pintype "passive"))
    )
    (net (code "66") (name "Net-(D3-A)") (class "Default")
      (node (ref "D3") (pin "2") (pinfunction "A_2") (pintype "passive"))
      (node (ref "R13") (pin "1") (pinfunction "1_1") (pintype "passive"))
    )
    (net (code "67") (name "Net-(M1-+3.3VD_IN-Pad25)") (class "Default")
      (node (ref "M1") (pin "25") (pinfunction "+3.3VD_IN_25") (pintype "power_in"))
      (node (ref "M1") (pin "26") (pinfunction "+3.3VD_IN_26") (pintype "power_in"))
      (node (ref "R11") (pin "2") (pinfunction "2_2") (pintype "passive"))
      (node (ref "R12") (pin "2") (pinfunction "2_2") (pintype "passive"))
    )
    (net (code "68") (name "Net-(TP1-PP)") (class "Default")
      (node (ref "TP1") (pin "1") (pinfunction "PP_1") (pintype "passive"))
      (node (ref "U3") (pin "1") (pinfunction "RI_1") (pintype "input"))
    )
    (net (code "69") (name "Net-(TP3-PP)") (class "Default")
      (node (ref "TP3") (pin "1") (pinfunction "PP_1") (pintype "passive"))
      (node (ref "U3") (pin "11") (pinfunction "GPIO.3_11") (pintype "bidirectional"))
    )
    (net (code "70") (name "Net-(TP4-PP)") (class "Default")
      (node (ref "TP4") (pin "1") (pinfunction "PP_1") (pintype "passive"))
      (node (ref "U3") (pin "12") (pinfunction "GPIO.2_12") (pintype "bidirectional"))
    )
    (net (code "71") (name "Net-(TP5-PP)") (class "Default")
      (node (ref "TP5") (pin "1") (pinfunction "PP_1") (pintype "passive"))
      (node (ref "U3") (pin "13") (pinfunction "GPIO.1_13") (pintype "bidirectional"))
    )
    (net (code "72") (name "Net-(TP6-PP)") (class "Default")
      (node (ref "TP6") (pin "1") (pinfunction "PP_1") (pintype "passive"))
      (node (ref "U3") (pin "14") (pinfunction "GPIO.0_14") (pintype "bidirectional"))
    )
    (net (code "73") (name "Net-(TP9-PP)") (class "Default")
      (node (ref "TP9") (pin "1") (pinfunction "PP_1") (pintype "passive"))
      (node (ref "U3") (pin "22") (pinfunction "DSR_22") (pintype "input"))
    )
    (net (code "74") (name "Net-(TP10-PP)") (class "Default")
      (node (ref "TP10") (pin "1") (pinfunction "PP_1") (pintype "passive"))
      (node (ref "U3") (pin "23") (pinfunction "DTR_23") (pintype "output"))
    )
    (net (code "75") (name "Net-(TP11-PP)") (class "Default")
      (node (ref "TP11") (pin "1") (pinfunction "PP_1") (pintype "passive"))
      (node (ref "U3") (pin "24") (pinfunction "DCD_24") (pintype "input"))
    )
    (net (code "76") (name "Net-(U3-VDD)") (class "Default")
      (node (ref "C10") (pin "1") (pinfunction "1_1") (pintype "passive"))
      (node (ref "C9") (pin "1") (pinfunction "1_1") (pintype "passive"))
      (node (ref "U3") (pin "6") (pinfunction "VDD_6") (pintype "power_in"))
    )
    (net (code "77") (name "Net-(U3-VPP)") (class "Default")
      (node (ref "C19") (pin "1") (pinfunction "1_1") (pintype "passive"))
      (node (ref "U3") (pin "16") (pinfunction "VPP_16") (pintype "passive"))
    )
    (net (code "78") (name "PE") (class "Default")
      (node (ref "C2") (pin "1") (pinfunction "1_1") (pintype "passive"))
      (node (ref "S1") (pin "SH$1") (pinfunction "M0_SH$1") (pintype "passive"))
      (node (ref "S1") (pin "SH$2") (pinfunction "M1_SH$2") (pintype "passive"))
      (node (ref "S1") (pin "SH$3") (pinfunction "M2_SH$3") (pintype "passive"))
      (node (ref "S1") (pin "SH$4") (pinfunction "M3_SH$4") (pintype "passive"))
    )
    (net (code "79") (name "unconnected-(S1-Pad4)") (class "Default")
      (node (ref "S1") (pin "4") (pinfunction "4_4") (pintype "passive"))
    )
    (net (code "80") (name "unconnected-(U2-PG-Pad8)") (class "Default")
      (node (ref "U2") (pin "8") (pinfunction "PG_8") (pintype "open_collector"))
    )
    (net (code "81") (name "unconnected-(U3-NC-Pad10)") (class "Default")
      (node (ref "U3") (pin "10") (pinfunction "NC_10") (pintype "no_connect"))
    )
    (net (code "82") (name "unconnected-(U3-SUSPEND-Pad17)") (class "Default")
      (node (ref "U3") (pin "17") (pinfunction "SUSPEND_17") (pintype "output"))
    )
    (net (code "83") (name "unconnected-(U3-~{RST}-Pad9)") (class "Default")
      (node (ref "U3") (pin "9") (pinfunction "~{RST}_9") (pintype "bidirectional"))
    )
    (net (code "84") (name "unconnected-(U3-~{SUSPEND}-Pad15)") (class "Default")
      (node (ref "U3") (pin "15") (pinfunction "~{SUSPEND}_15") (pintype "output"))
    )
  )
)
